# NG2092_MICS.net
KiCad netlist of a schematic drawn in Altium Designer
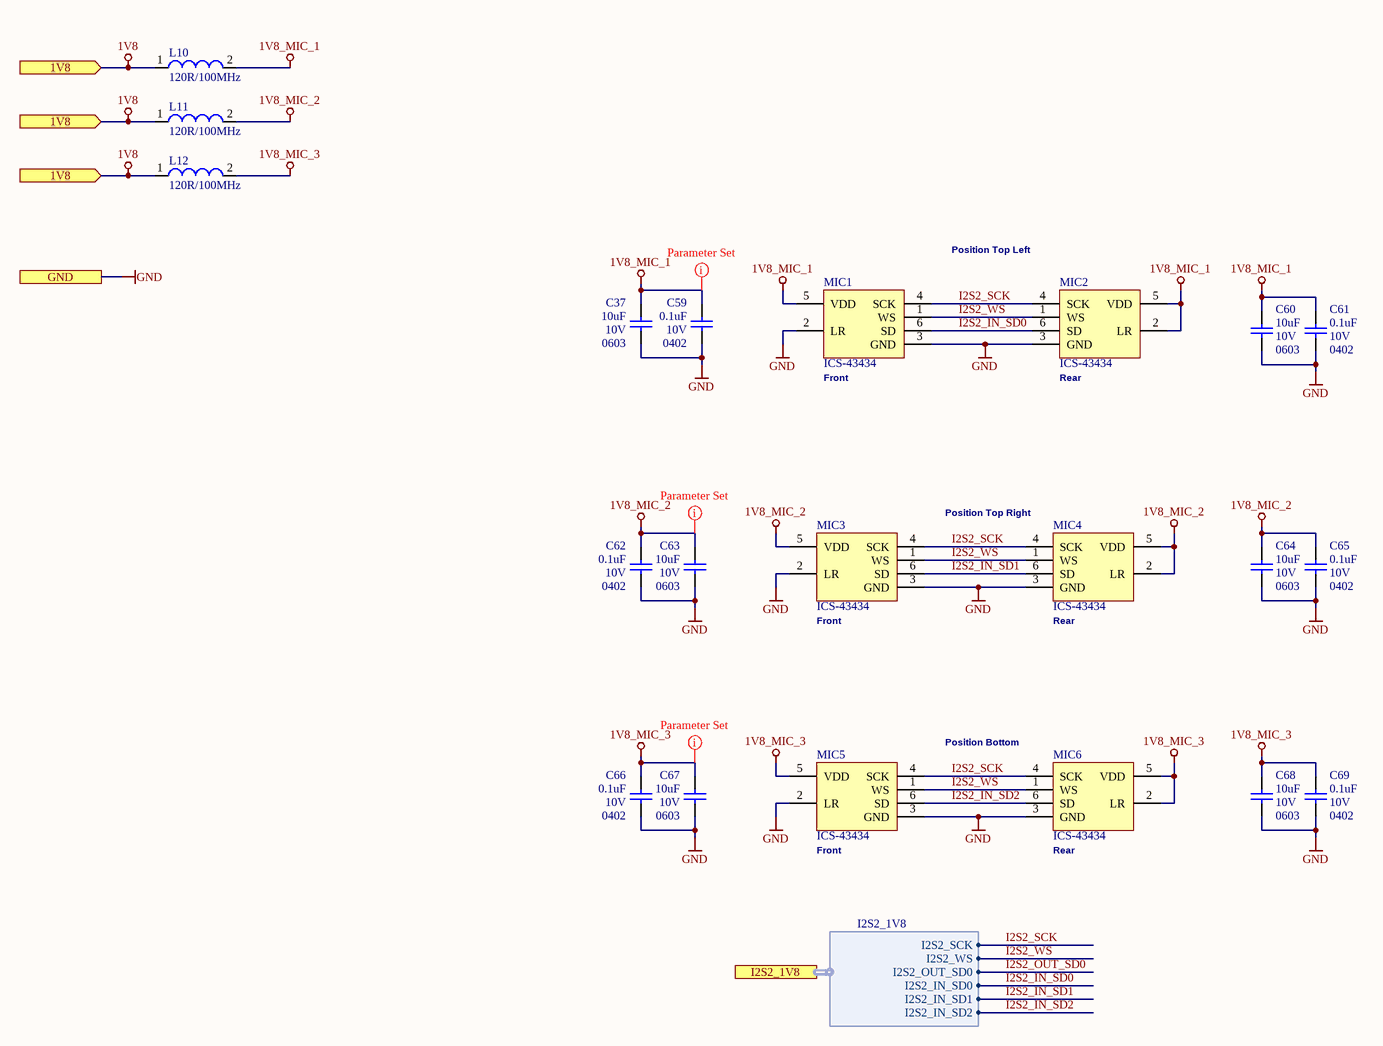
[diagram p0: NG2092_MICS.SchDoc]

(export (version "E")
  (design (tool "Eeschema 10.0.6"))
  (components
    (comp (ref "C37")
      (value "10uF 0603")
      (footprint "CAP_Altium_Vault_Generic:CAPC0603(1608)100_L")
      (description "CAP CER 10UF 10V X5R 0603 20%")
      (fields
        (field (name "CASE CODE (IMPERIAL)") "0603")
        (field (name "TOLERANCE") "20%")
        (field (name "CAPACITANCE") "10uF")
        (field (name "VOLTAGE RATING") "10V")
      )
      (libsource (lib "LuxonisMaster") (part "GRM188R61A106ME69D"))
    )
    (comp (ref "C59")
      (value "0.1uF 0402")
      (footprint "CAP_Altium_Vault_Generic:CAPC0402(1005)70_L")
      (description "CAP CER 0.1UF 10V X7R 0402 5%")
      (fields
        (field (name "CASE/PACKAGE") "0402")
        (field (name "CAPACITANCE") "0.1uF")
        (field (name "TOLERANCE") "5%")
        (field (name "VOLTAGE RATING") "10V")
      )
      (libsource (lib "LuxonisMaster") (part "GRM155R71A104JA01D"))
    )
    (comp (ref "C60")
      (value "10uF 0603")
      (footprint "CAP_Altium_Vault_Generic:CAPC0603(1608)100_L")
      (description "CAP CER 10UF 10V X5R 0603 20%")
      (fields
        (field (name "CASE CODE (IMPERIAL)") "0603")
        (field (name "TOLERANCE") "20%")
        (field (name "CAPACITANCE") "10uF")
        (field (name "VOLTAGE RATING") "10V")
      )
      (libsource (lib "LuxonisMaster") (part "GRM188R61A106ME69D"))
    )
    (comp (ref "C61")
      (value "0.1uF 0402")
      (footprint "CAP_Altium_Vault_Generic:CAPC0402(1005)70_L")
      (description "CAP CER 0.1UF 10V X7R 0402 5%")
      (fields
        (field (name "CASE/PACKAGE") "0402")
        (field (name "CAPACITANCE") "0.1uF")
        (field (name "TOLERANCE") "5%")
        (field (name "VOLTAGE RATING") "10V")
      )
      (libsource (lib "LuxonisMaster") (part "GRM155R71A104JA01D"))
    )
    (comp (ref "C62")
      (value "0.1uF 0402")
      (footprint "CAP_Altium_Vault_Generic:CAPC0402(1005)70_L")
      (description "CAP CER 0.1UF 10V X7R 0402 5%")
      (fields
        (field (name "CASE/PACKAGE") "0402")
        (field (name "CAPACITANCE") "0.1uF")
        (field (name "TOLERANCE") "5%")
        (field (name "VOLTAGE RATING") "10V")
      )
      (libsource (lib "LuxonisMaster") (part "GRM155R71A104JA01D"))
    )
    (comp (ref "C63")
      (value "10uF 0603")
      (footprint "CAP_Altium_Vault_Generic:CAPC0603(1608)100_L")
      (description "CAP CER 10UF 10V X5R 0603 20%")
      (fields
        (field (name "CASE CODE (IMPERIAL)") "0603")
        (field (name "TOLERANCE") "20%")
        (field (name "CAPACITANCE") "10uF")
        (field (name "VOLTAGE RATING") "10V")
      )
      (libsource (lib "LuxonisMaster") (part "GRM188R61A106ME69D"))
    )
    (comp (ref "C64")
      (value "10uF 0603")
      (footprint "CAP_Altium_Vault_Generic:CAPC0603(1608)100_L")
      (description "CAP CER 10UF 10V X5R 0603 20%")
      (fields
        (field (name "CASE CODE (IMPERIAL)") "0603")
        (field (name "TOLERANCE") "20%")
        (field (name "CAPACITANCE") "10uF")
        (field (name "VOLTAGE RATING") "10V")
      )
      (libsource (lib "LuxonisMaster") (part "GRM188R61A106ME69D"))
    )
    (comp (ref "C65")
      (value "0.1uF 0402")
      (footprint "CAP_Altium_Vault_Generic:CAPC0402(1005)70_L")
      (description "CAP CER 0.1UF 10V X7R 0402 5%")
      (fields
        (field (name "CASE/PACKAGE") "0402")
        (field (name "CAPACITANCE") "0.1uF")
        (field (name "TOLERANCE") "5%")
        (field (name "VOLTAGE RATING") "10V")
      )
      (libsource (lib "LuxonisMaster") (part "GRM155R71A104JA01D"))
    )
    (comp (ref "C66")
      (value "0.1uF 0402")
      (footprint "CAP_Altium_Vault_Generic:CAPC0402(1005)70_L")
      (description "CAP CER 0.1UF 10V X7R 0402 5%")
      (fields
        (field (name "CASE/PACKAGE") "0402")
        (field (name "CAPACITANCE") "0.1uF")
        (field (name "TOLERANCE") "5%")
        (field (name "VOLTAGE RATING") "10V")
      )
      (libsource (lib "LuxonisMaster") (part "GRM155R71A104JA01D"))
    )
    (comp (ref "C67")
      (value "10uF 0603")
      (footprint "CAP_Altium_Vault_Generic:CAPC0603(1608)100_L")
      (description "CAP CER 10UF 10V X5R 0603 20%")
      (fields
        (field (name "CASE CODE (IMPERIAL)") "0603")
        (field (name "TOLERANCE") "20%")
        (field (name "CAPACITANCE") "10uF")
        (field (name "VOLTAGE RATING") "10V")
      )
      (libsource (lib "LuxonisMaster") (part "GRM188R61A106ME69D"))
    )
    (comp (ref "C68")
      (value "10uF 0603")
      (footprint "CAP_Altium_Vault_Generic:CAPC0603(1608)100_L")
      (description "CAP CER 10UF 10V X5R 0603 20%")
      (fields
        (field (name "CASE CODE (IMPERIAL)") "0603")
        (field (name "TOLERANCE") "20%")
        (field (name "CAPACITANCE") "10uF")
        (field (name "VOLTAGE RATING") "10V")
      )
      (libsource (lib "LuxonisMaster") (part "GRM188R61A106ME69D"))
    )
    (comp (ref "C69")
      (value "0.1uF 0402")
      (footprint "CAP_Altium_Vault_Generic:CAPC0402(1005)70_L")
      (description "CAP CER 0.1UF 10V X7R 0402 5%")
      (fields
        (field (name "CASE/PACKAGE") "0402")
        (field (name "CAPACITANCE") "0.1uF")
        (field (name "TOLERANCE") "5%")
        (field (name "VOLTAGE RATING") "10V")
      )
      (libsource (lib "LuxonisMaster") (part "GRM155R71A104JA01D"))
    )
    (comp (ref "L10")
      (value "120R/100MHz")
      (footprint "LuxonisMaster:BLM18PG121SN1D_N")
      (description "FERRITE BEAD 120 OHM 0603 1LN")
      (fields (field (name "TOLERANCE") "25%"))
      (libsource (lib "LuxonisMaster") (part "BLM18PG121SN1D"))
    )
    (comp (ref "L11")
      (value "120R/100MHz")
      (footprint "LuxonisMaster:BLM18PG121SN1D_N")
      (description "FERRITE BEAD 120 OHM 0603 1LN")
      (fields (field (name "TOLERANCE") "25%"))
      (libsource (lib "LuxonisMaster") (part "BLM18PG121SN1D"))
    )
    (comp (ref "L12")
      (value "120R/100MHz")
      (footprint "LuxonisMaster:BLM18PG121SN1D_N")
      (description "FERRITE BEAD 120 OHM 0603 1LN")
      (fields (field (name "TOLERANCE") "25%"))
      (libsource (lib "LuxonisMaster") (part "BLM18PG121SN1D"))
    )
    (comp (ref "MIC1")
      (value "ICS-43434")
      (footprint "ICS-43434")
      (libsource (lib "NG2092") (part "ICS-43434"))
    )
    (comp (ref "MIC2") (value "ICS-43434") (footprint "ICS-43434") (libsource (lib "") (part "ICS-43434_1")))
    (comp (ref "MIC3")
      (value "ICS-43434")
      (footprint "ICS-43434")
      (libsource (lib "NG2092") (part "ICS-43434"))
    )
    (comp (ref "MIC4") (value "ICS-43434") (footprint "ICS-43434") (libsource (lib "") (part "ICS-43434_1")))
    (comp (ref "MIC5")
      (value "ICS-43434")
      (footprint "ICS-43434")
      (libsource (lib "NG2092") (part "ICS-43434"))
    )
    (comp (ref "MIC6") (value "ICS-43434") (footprint "ICS-43434") (libsource (lib "") (part "ICS-43434_1")))
  )
  (nets
    (net (code "2") (name "/I2S2_IN_SD0") (class "Default")
      (node (ref "MIC1") (pin "6") (pinfunction "SD_6") (pintype "passive"))
      (node (ref "MIC2") (pin "6") (pinfunction "SD_6") (pintype "passive"))
    )
    (net (code "3") (name "/I2S2_IN_SD1") (class "Default")
      (node (ref "MIC3") (pin "6") (pinfunction "SD_6") (pintype "passive"))
      (node (ref "MIC4") (pin "6") (pinfunction "SD_6") (pintype "passive"))
    )
    (net (code "4") (name "/I2S2_IN_SD2") (class "Default")
      (node (ref "MIC5") (pin "6") (pinfunction "SD_6") (pintype "passive"))
      (node (ref "MIC6") (pin "6") (pinfunction "SD_6") (pintype "passive"))
    )
    (net (code "6") (name "/I2S2_SCK") (class "Default")
      (node (ref "MIC1") (pin "4") (pinfunction "SCK_4") (pintype "passive"))
      (node (ref "MIC2") (pin "4") (pinfunction "SCK_4") (pintype "passive"))
      (node (ref "MIC3") (pin "4") (pinfunction "SCK_4") (pintype "passive"))
      (node (ref "MIC4") (pin "4") (pinfunction "SCK_4") (pintype "passive"))
      (node (ref "MIC5") (pin "4") (pinfunction "SCK_4") (pintype "passive"))
      (node (ref "MIC6") (pin "4") (pinfunction "SCK_4") (pintype "passive"))
    )
    (net (code "7") (name "/I2S2_WS") (class "Default")
      (node (ref "MIC1") (pin "1") (pinfunction "WS_1") (pintype "passive"))
      (node (ref "MIC2") (pin "1") (pinfunction "WS_1") (pintype "passive"))
      (node (ref "MIC3") (pin "1") (pinfunction "WS_1") (pintype "passive"))
      (node (ref "MIC4") (pin "1") (pinfunction "WS_1") (pintype "passive"))
      (node (ref "MIC5") (pin "1") (pinfunction "WS_1") (pintype "passive"))
      (node (ref "MIC6") (pin "1") (pinfunction "WS_1") (pintype "passive"))
    )
    (net (code "9") (name "1V8") (class "Default")
      (node (ref "L10") (pin "1") (pinfunction "1_1") (pintype "passive"))
      (node (ref "L11") (pin "1") (pinfunction "1_1") (pintype "passive"))
      (node (ref "L12") (pin "1") (pinfunction "1_1") (pintype "passive"))
    )
    (net (code "10") (name "1V8_MIC_1") (class "Default")
      (node (ref "C37") (pin "2") (pinfunction "2_2") (pintype "passive"))
      (node (ref "C59") (pin "2") (pinfunction "2_2") (pintype "passive"))
      (node (ref "C60") (pin "2") (pinfunction "2_2") (pintype "passive"))
      (node (ref "C61") (pin "2") (pinfunction "2_2") (pintype "passive"))
      (node (ref "L10") (pin "2") (pinfunction "2_2") (pintype "passive"))
      (node (ref "MIC1") (pin "5") (pinfunction "VDD_5") (pintype "passive"))
      (node (ref "MIC2") (pin "2") (pinfunction "LR_2") (pintype "passive"))
      (node (ref "MIC2") (pin "5") (pinfunction "VDD_5") (pintype "passive"))
    )
    (net (code "11") (name "1V8_MIC_2") (class "Default")
      (node (ref "C62") (pin "2") (pinfunction "2_2") (pintype "passive"))
      (node (ref "C63") (pin "2") (pinfunction "2_2") (pintype "passive"))
      (node (ref "C64") (pin "2") (pinfunction "2_2") (pintype "passive"))
      (node (ref "C65") (pin "2") (pinfunction "2_2") (pintype "passive"))
      (node (ref "L11") (pin "2") (pinfunction "2_2") (pintype "passive"))
      (node (ref "MIC3") (pin "5") (pinfunction "VDD_5") (pintype "passive"))
      (node (ref "MIC4") (pin "2") (pinfunction "LR_2") (pintype "passive"))
      (node (ref "MIC4") (pin "5") (pinfunction "VDD_5") (pintype "passive"))
    )
    (net (code "12") (name "1V8_MIC_3") (class "Default")
      (node (ref "C66") (pin "2") (pinfunction "2_2") (pintype "passive"))
      (node (ref "C67") (pin "2") (pinfunction "2_2") (pintype "passive"))
      (node (ref "C68") (pin "2") (pinfunction "2_2") (pintype "passive"))
      (node (ref "C69") (pin "2") (pinfunction "2_2") (pintype "passive"))
      (node (ref "L12") (pin "2") (pinfunction "2_2") (pintype "passive"))
      (node (ref "MIC5") (pin "5") (pinfunction "VDD_5") (pintype "passive"))
      (node (ref "MIC6") (pin "2") (pinfunction "LR_2") (pintype "passive"))
      (node (ref "MIC6") (pin "5") (pinfunction "VDD_5") (pintype "passive"))
    )
    (net (code "13") (name "GND") (class "Default")
      (node (ref "C37") (pin "1") (pinfunction "1_1") (pintype "passive"))
      (node (ref "C59") (pin "1") (pinfunction "1_1") (pintype "passive"))
      (node (ref "C60") (pin "1") (pinfunction "1_1") (pintype "passive"))
      (node (ref "C61") (pin "1") (pinfunction "1_1") (pintype "passive"))
      (node (ref "C62") (pin "1") (pinfunction "1_1") (pintype "passive"))
      (node (ref "C63") (pin "1") (pinfunction "1_1") (pintype "passive"))
      (node (ref "C64") (pin "1") (pinfunction "1_1") (pintype "passive"))
      (node (ref "C65") (pin "1") (pinfunction "1_1") (pintype "passive"))
      (node (ref "C66") (pin "1") (pinfunction "1_1") (pintype "passive"))
      (node (ref "C67") (pin "1") (pinfunction "1_1") (pintype "passive"))
      (node (ref "C68") (pin "1") (pinfunction "1_1") (pintype "passive"))
      (node (ref "C69") (pin "1") (pinfunction "1_1") (pintype "passive"))
      (node (ref "MIC1") (pin "2") (pinfunction "LR_2") (pintype "passive"))
      (node (ref "MIC1") (pin "3") (pinfunction "GND_3") (pintype "passive"))
      (node (ref "MIC2") (pin "3") (pinfunction "GND_3") (pintype "passive"))
      (node (ref "MIC3") (pin "2") (pinfunction "LR_2") (pintype "passive"))
      (node (ref "MIC3") (pin "3") (pinfunction "GND_3") (pintype "passive"))
      (node (ref "MIC4") (pin "3") (pinfunction "GND_3") (pintype "passive"))
      (node (ref "MIC5") (pin "2") (pinfunction "LR_2") (pintype "passive"))
      (node (ref "MIC5") (pin "3") (pinfunction "GND_3") (pintype "passive"))
      (node (ref "MIC6") (pin "3") (pinfunction "GND_3") (pintype "passive"))
    )
  )
)
